# Main.net
KiCad netlist of a schematic drawn in Altium Designer
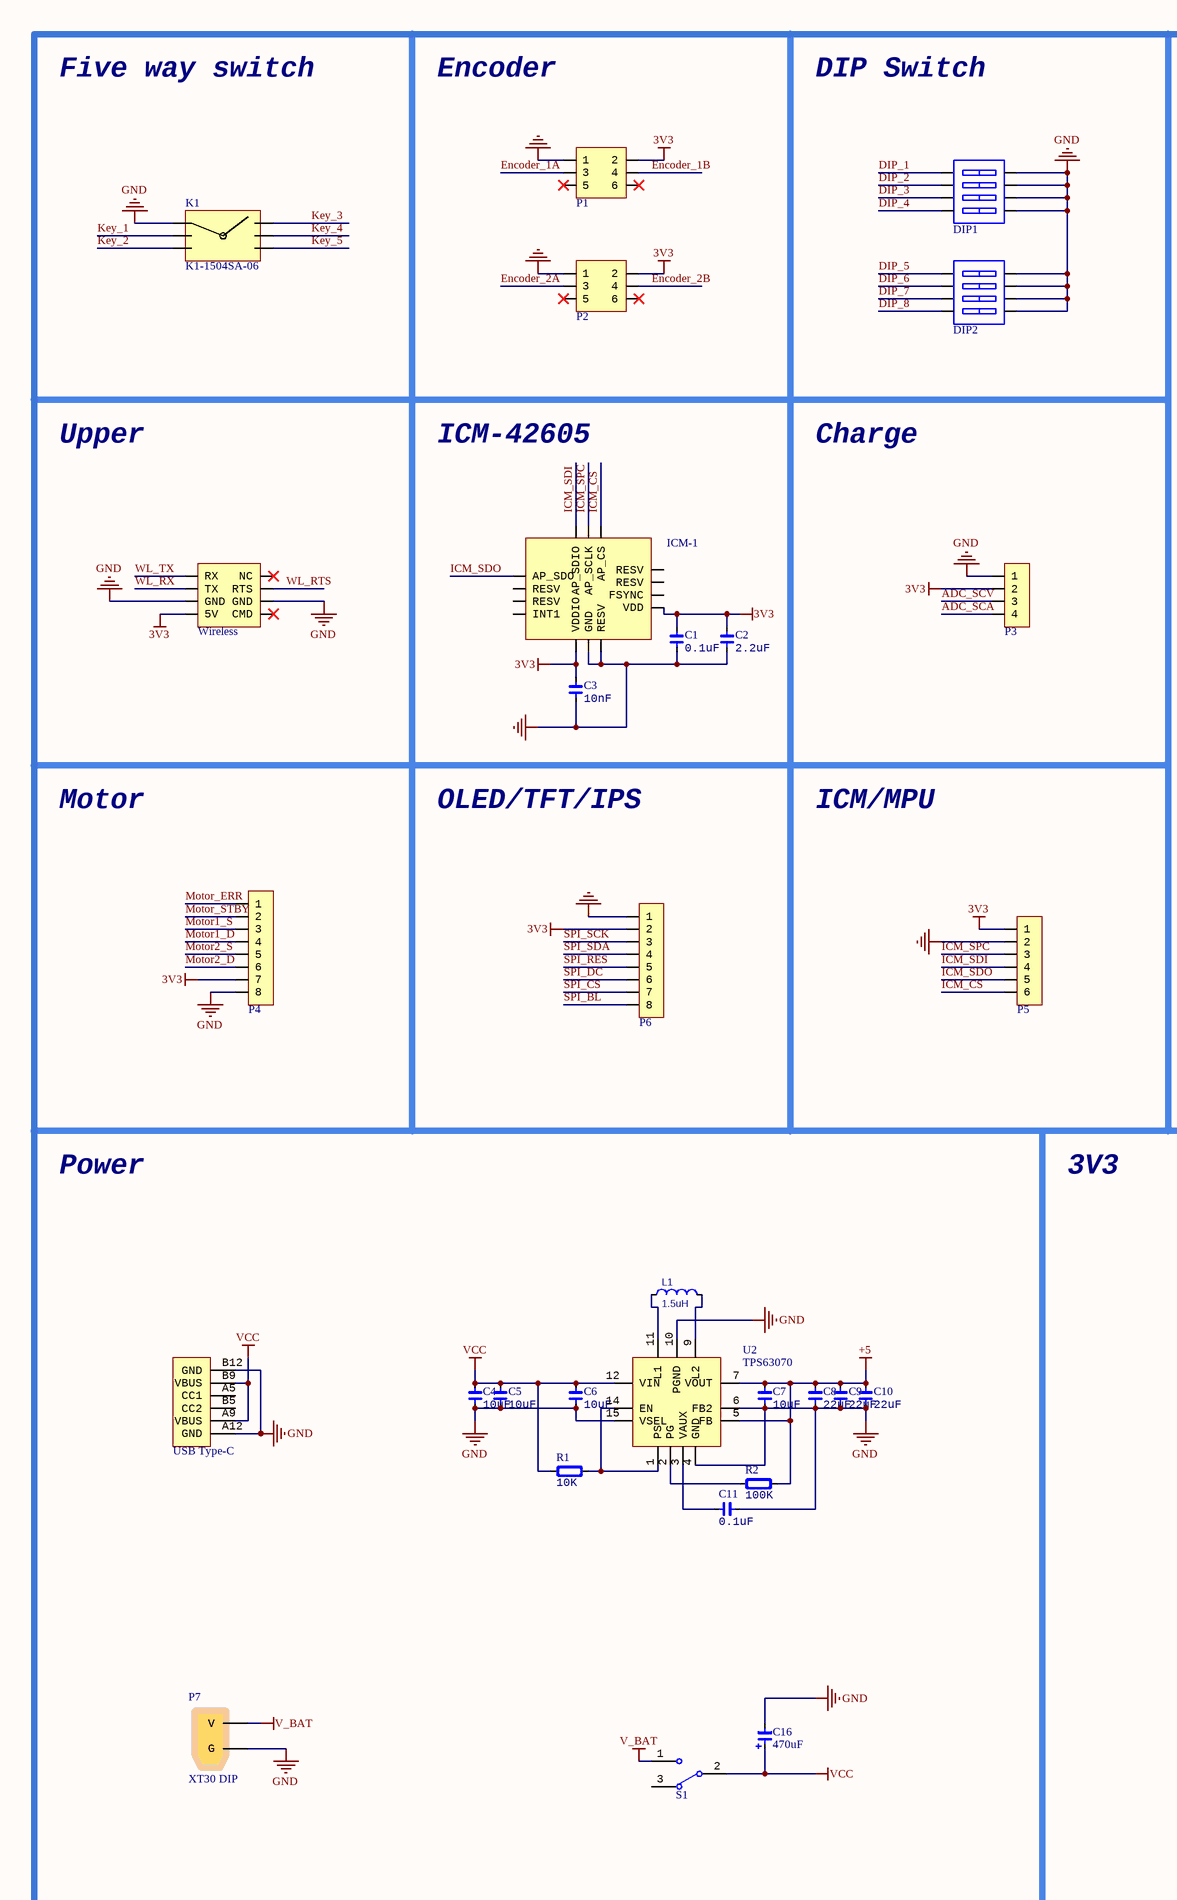
[diagram p0: Main.SchDoc, left]
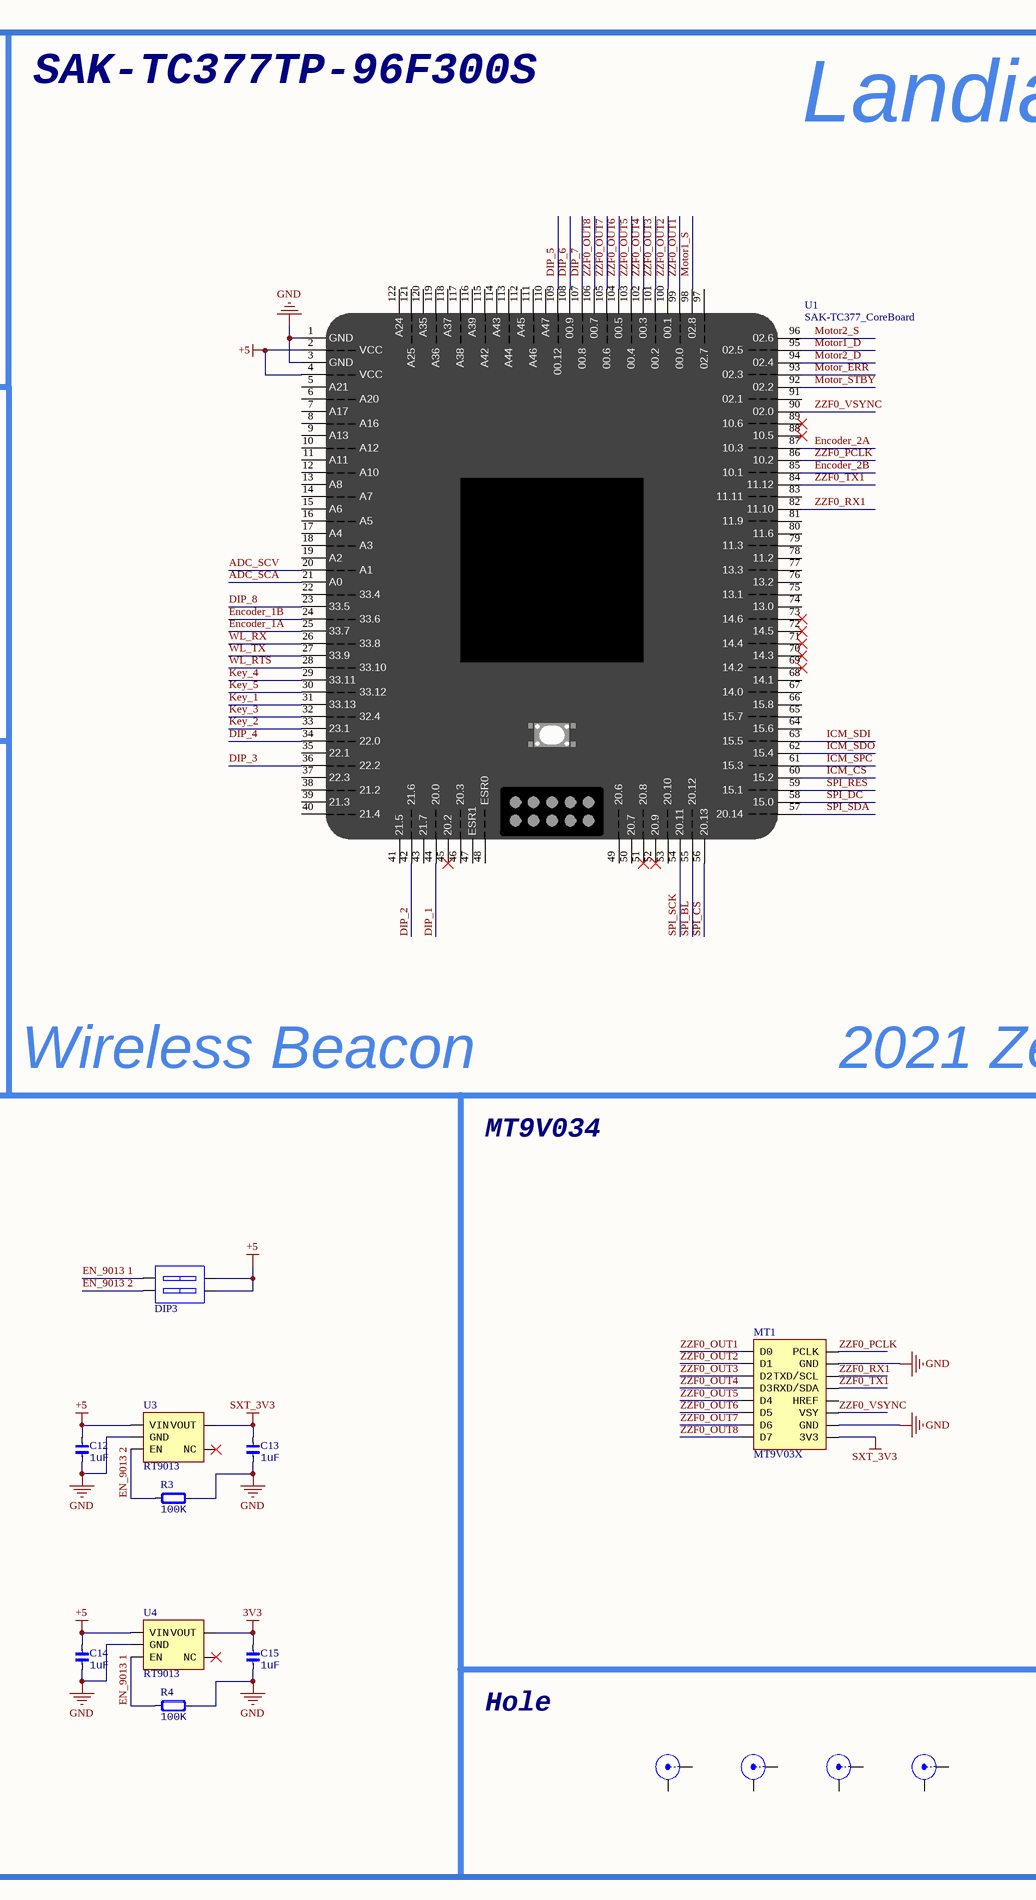
[diagram p1: Main.SchDoc, right]

(export (version "E")
  (design (tool "Eeschema 10.0.6"))
  (components
    (comp (ref "C1")
      (value "0.1uF")
      (footprint "0805_CAP")
      (description "Capacitor")
      (libsource (lib "") (part "0805_CAP_1"))
    )
    (comp (ref "C2")
      (value "2.2uF")
      (footprint "0805_CAP")
      (description "Capacitor")
      (libsource (lib "") (part "0805_CAP_1"))
    )
    (comp (ref "C3")
      (value "10nF")
      (footprint "0805_CAP")
      (description "Capacitor")
      (libsource (lib "") (part "0805_CAP_1"))
    )
    (comp (ref "C4")
      (value "10uF")
      (footprint "0805_CAP")
      (description "Capacitor")
      (libsource (lib "Beacon") (part "0805_CAP"))
    )
    (comp (ref "C5")
      (value "10uF")
      (footprint "0805_CAP")
      (description "Capacitor")
      (libsource (lib "Beacon") (part "0805_CAP"))
    )
    (comp (ref "C6")
      (value "10uF")
      (footprint "0603_CAP")
      (description "Capacitor")
      (libsource (lib "Beacon") (part "0603_CAP"))
    )
    (comp (ref "C7")
      (value "10uF")
      (footprint "0603_CAP")
      (description "Capacitor")
      (libsource (lib "Beacon") (part "0603_CAP"))
    )
    (comp (ref "C8")
      (value "22uF")
      (footprint "0805_CAP")
      (description "Capacitor")
      (libsource (lib "Beacon") (part "0805_CAP"))
    )
    (comp (ref "C9")
      (value "22uF")
      (footprint "0805_CAP")
      (description "Capacitor")
      (libsource (lib "Beacon") (part "0805_CAP"))
    )
    (comp (ref "C10")
      (value "22uF")
      (footprint "0805_CAP")
      (description "Capacitor")
      (libsource (lib "Beacon") (part "0805_CAP"))
    )
    (comp (ref "C11")
      (value "0.1uF")
      (footprint "0805_CAP")
      (description "Capacitor")
      (libsource (lib "") (part "0805_CAP_2"))
    )
    (comp (ref "C12")
      (value "1uF")
      (footprint "0805_CAP")
      (description "Capacitor")
      (libsource (lib "Beacon") (part "0805_CAP"))
    )
    (comp (ref "C13")
      (value "1uF")
      (footprint "0805_CAP")
      (description "Capacitor")
      (libsource (lib "Beacon") (part "0805_CAP"))
    )
    (comp (ref "C14")
      (value "1uF")
      (footprint "0805_CAP")
      (description "Capacitor")
      (libsource (lib "Beacon") (part "0805_CAP"))
    )
    (comp (ref "C15")
      (value "1uF")
      (footprint "0805_CAP")
      (description "Capacitor")
      (libsource (lib "Beacon") (part "0805_CAP"))
    )
    (comp (ref "C16")
      (value "470uF")
      (footprint "CAP_8X10")
      (description "Electrolytic capacitor")
      (libsource (lib "Beacon") (part "CAP_10"))
    )
    (comp (ref "DIP1")
      (value "CSW-4P_SMD")
      (footprint "DIP Switch 4P - SMD")
      (fields (field (name "版权归属") "源创客"))
      (libsource (lib "Beacon") (part "CSW-4P_SMD"))
    )
    (comp (ref "DIP2")
      (value "CSW-4P_SMD")
      (footprint "DIP Switch 4P - SMD")
      (fields (field (name "版权归属") "源创客"))
      (libsource (lib "Beacon") (part "CSW-4P_SMD"))
    )
    (comp (ref "DIP3")
      (value "CSW-2P")
      (footprint "DIP Switch 2P")
      (description "2路编码开关")
      (fields (field (name "版权归属") "源创客"))
      (libsource (lib "Beacon") (part "CSW-2P"))
    )
    (comp (ref "Hole1") (value "Hole") (footprint "Hole") (libsource (lib "Beacon") (part "Hole")))
    (comp (ref "Hole2") (value "Hole") (footprint "Hole") (libsource (lib "Beacon") (part "Hole")))
    (comp (ref "Hole3") (value "Hole") (footprint "Hole") (libsource (lib "Beacon") (part "Hole")))
    (comp (ref "Hole4") (value "Hole") (footprint "Hole") (libsource (lib "Beacon") (part "Hole")))
    (comp (ref "ICM-1")
      (value "ICM-42605")
      (footprint "LGA-14_L3.0-W2.5-P0.50-TL")
      (libsource (lib "Beacon") (part "ICM-42605"))
    )
    (comp (ref "K1")
      (value "K1-1504SA-06")
      (footprint "SW-SMD_K1-1504SA-06")
      (description "K1-1504SA-06 五向开关")
      (libsource (lib "Beacon") (part "K1-1504SA-06"))
    )
    (comp (ref "L1")
      (value "1.5uH")
      (footprint "CDRH74R")
      (description "Inductor")
      (fields
        (field (name "BOM_SUPPLIER PART") "C696490")
        (field (name "BOM_MANUFACTURER PART") "MPIT6045-330M-LF")
        (field (name "CONTRIBUTOR") "LCSC")
      )
      (libsource (lib "Beacon") (part "IND"))
    )
    (comp (ref "MT1")
      (value "MT9V03X")
      (footprint "MT9V034")
      (description "MT9V03X转接板")
      (libsource (lib "Beacon") (part "MT9V03X"))
    )
    (comp (ref "P1")
      (value "HDR2x3_2.54")
      (footprint "HDR_2X3")
      (description "Header")
      (libsource (lib "TC264DA") (part "HDR2x3_2.54"))
    )
    (comp (ref "P2")
      (value "HDR2x3_2.54")
      (footprint "HDR_2X3")
      (description "Header")
      (libsource (lib "TC264DA") (part "HDR2x3_2.54"))
    )
    (comp (ref "P3")
      (value "HDR1x4_2.54")
      (footprint "HDR_1X4")
      (description "Header")
      (libsource (lib "Beacon") (part "HDR1x4_2.54"))
    )
    (comp (ref "P4")
      (value "HDR1x8_2.54_F")
      (footprint "HDR_1X8_F")
      (description "Header")
      (libsource (lib "Beacon") (part "HDR1x8_2.54_F"))
    )
    (comp (ref "P5")
      (value "HDR1x6_2.54")
      (footprint "HDR_1X6")
      (description "Header")
      (libsource (lib "Beacon") (part "HDR1x6_2.54"))
    )
    (comp (ref "P6")
      (value "HDR1x8_2.54_F")
      (footprint "HDR_1X8_F")
      (description "Header")
      (libsource (lib "Beacon") (part "HDR1x8_2.54_F"))
    )
    (comp (ref "P7")
      (value "XT30 DIP")
      (footprint "XT30 DIP")
      (description "XT30 板载直头直插")
      (libsource (lib "Beacon") (part "XT30 DIP"))
    )
    (comp (ref "R1")
      (value "10K")
      (footprint "0805_RES")
      (description "Resistor")
      (libsource (lib "Beacon") (part "0805_RES"))
    )
    (comp (ref "R2")
      (value "100K")
      (footprint "0805_RES")
      (description "Resistor")
      (libsource (lib "Beacon") (part "0805_RES"))
    )
    (comp (ref "R3")
      (value "100K")
      (footprint "0805_RES")
      (description "Resistor")
      (libsource (lib "Beacon") (part "0805_RES"))
    )
    (comp (ref "R4")
      (value "100K")
      (footprint "0805_RES")
      (description "Resistor")
      (libsource (lib "Beacon") (part "0805_RES"))
    )
    (comp (ref "S1") (value "SMTS-102") (footprint "SMTS-102") (libsource (lib "Beacon") (part "SMTS-102")))
    (comp (ref "Type-C1")
      (value "USB Type-C")
      (footprint "Type-C 6P")
      (description "Type-C 6P")
      (libsource (lib "Beacon") (part "USB_Type-C_6P"))
    )
    (comp (ref "U1")
      (value "SAK-TC377_CoreBoard")
      (footprint "TC377_CoreBoard")
      (description "逐飞科技TC377核心板")
      (libsource (lib "Beacon") (part "SAK-TC377_CoreBoard"))
    )
    (comp (ref "U2")
      (value "TPS63070")
      (footprint "VQFN-15_L3.0-W2.5-P0.50-BL")
      (libsource (lib "Beacon") (part "TPS63070"))
    )
    (comp (ref "U3")
      (value "RT9013")
      (footprint "SOT-23-5_L3.0-W1.7-P0.95-LS2.8-BR")
      (libsource (lib "Beacon") (part "RT9013"))
    )
    (comp (ref "U4")
      (value "RT9013")
      (footprint "SOT-23-5_L3.0-W1.7-P0.95-LS2.8-BR")
      (libsource (lib "Beacon") (part "RT9013"))
    )
    (comp (ref "Wireless1")
      (value "Wireless")
      (footprint "HDR_2X4_F")
      (libsource (lib "Beacon") (part "Wireless"))
    )
  )
  (nets
    (net (code "1") (name "+5") (class "Default")
      (node (ref "C10") (pin "2") (pinfunction "2_2") (pintype "passive"))
      (node (ref "C12") (pin "2") (pinfunction "2_2") (pintype "passive"))
      (node (ref "C14") (pin "2") (pinfunction "2_2") (pintype "passive"))
      (node (ref "C7") (pin "2") (pinfunction "2_2") (pintype "passive"))
      (node (ref "C8") (pin "2") (pinfunction "2_2") (pintype "passive"))
      (node (ref "C9") (pin "2") (pinfunction "2_2") (pintype "passive"))
      (node (ref "DIP3") (pin "4") (pinfunction "4_4") (pintype "passive"))
      (node (ref "DIP3") (pin "5") (pinfunction "5_5") (pintype "passive"))
      (node (ref "R2") (pin "2") (pinfunction "2_2") (pintype "passive"))
      (node (ref "U1") (pin "2") (pinfunction "VCC_2") (pintype "passive"))
      (node (ref "U1") (pin "4") (pinfunction "VCC_4") (pintype "passive"))
      (node (ref "U2") (pin "5") (pinfunction "FB_5") (pintype "passive"))
      (node (ref "U2") (pin "7") (pinfunction "VOUT_7") (pintype "passive"))
      (node (ref "U3") (pin "1") (pinfunction "VIN_1") (pintype "passive"))
      (node (ref "U4") (pin "1") (pinfunction "VIN_1") (pintype "passive"))
    )
    (net (code "2") (name "/ADC_SCA") (class "Default")
      (node (ref "P3") (pin "4") (pinfunction "4_4") (pintype "passive"))
      (node (ref "U1") (pin "21") (pinfunction "A0_21") (pintype "passive"))
    )
    (net (code "3") (name "/ADC_SCV") (class "Default")
      (node (ref "P3") (pin "3") (pinfunction "3_3") (pintype "passive"))
      (node (ref "U1") (pin "20") (pinfunction "A1_20") (pintype "passive"))
    )
    (net (code "4") (name "/DIP_1") (class "Default")
      (node (ref "DIP1") (pin "1") (pinfunction "1_1") (pintype "passive"))
      (node (ref "U1") (pin "44") (pinfunction "20.0_44") (pintype "passive"))
    )
    (net (code "5") (name "/DIP_2") (class "Default")
      (node (ref "DIP1") (pin "2") (pinfunction "2_2") (pintype "passive"))
      (node (ref "U1") (pin "42") (pinfunction "21.6_42") (pintype "passive"))
    )
    (net (code "6") (name "/DIP_3") (class "Default")
      (node (ref "DIP1") (pin "3") (pinfunction "3_3") (pintype "passive"))
      (node (ref "U1") (pin "36") (pinfunction "22.2_36") (pintype "passive"))
    )
    (net (code "7") (name "/DIP_4") (class "Default")
      (node (ref "DIP1") (pin "4") (pinfunction "4_4") (pintype "passive"))
      (node (ref "U1") (pin "34") (pinfunction "22.0_34") (pintype "passive"))
    )
    (net (code "8") (name "/DIP_5") (class "Default")
      (node (ref "DIP2") (pin "1") (pinfunction "1_1") (pintype "passive"))
      (node (ref "U1") (pin "109") (pinfunction "00.12_109") (pintype "passive"))
    )
    (net (code "9") (name "/DIP_6") (class "Default")
      (node (ref "DIP2") (pin "2") (pinfunction "2_2") (pintype "passive"))
      (node (ref "U1") (pin "108") (pinfunction "00.9_108") (pintype "passive"))
    )
    (net (code "10") (name "/DIP_7") (class "Default")
      (node (ref "DIP2") (pin "3") (pinfunction "3_3") (pintype "passive"))
      (node (ref "U1") (pin "107") (pinfunction "00.8_107") (pintype "passive"))
    )
    (net (code "11") (name "/DIP_8") (class "Default")
      (node (ref "DIP2") (pin "4") (pinfunction "4_4") (pintype "passive"))
      (node (ref "U1") (pin "23") (pinfunction "33.5_23") (pintype "passive"))
    )
    (net (code "12") (name "/EN_9013 1") (class "Default")
      (node (ref "DIP3") (pin "1") (pinfunction "1_1") (pintype "passive"))
      (node (ref "R4") (pin "1") (pinfunction "1_1") (pintype "passive"))
      (node (ref "U4") (pin "3") (pinfunction "EN_3") (pintype "passive"))
    )
    (net (code "13") (name "/EN_9013 2") (class "Default")
      (node (ref "DIP3") (pin "2") (pinfunction "2_2") (pintype "passive"))
      (node (ref "R3") (pin "1") (pinfunction "1_1") (pintype "passive"))
      (node (ref "U3") (pin "3") (pinfunction "EN_3") (pintype "passive"))
    )
    (net (code "14") (name "/Encoder_1A") (class "Default")
      (node (ref "P1") (pin "3") (pinfunction "3_3") (pintype "passive"))
      (node (ref "U1") (pin "25") (pinfunction "33.7_25") (pintype "passive"))
    )
    (net (code "15") (name "/Encoder_1B") (class "Default")
      (node (ref "P1") (pin "4") (pinfunction "4_4") (pintype "passive"))
      (node (ref "U1") (pin "24") (pinfunction "33.6_24") (pintype "passive"))
    )
    (net (code "16") (name "/Encoder_2A") (class "Default")
      (node (ref "P2") (pin "3") (pinfunction "3_3") (pintype "passive"))
      (node (ref "U1") (pin "87") (pinfunction "10.3_87") (pintype "passive"))
    )
    (net (code "17") (name "/Encoder_2B") (class "Default")
      (node (ref "P2") (pin "4") (pinfunction "4_4") (pintype "passive"))
      (node (ref "U1") (pin "85") (pinfunction "10.1_85") (pintype "passive"))
    )
    (net (code "18") (name "/ICM_CS") (class "Default")
      (node (ref "ICM-1") (pin "12") (pinfunction "AP_CS_12") (pintype "passive"))
      (node (ref "P5") (pin "6") (pinfunction "6_6") (pintype "passive"))
      (node (ref "U1") (pin "60") (pinfunction "15.2_60") (pintype "passive"))
    )
    (net (code "19") (name "/ICM_SDI") (class "Default")
      (node (ref "ICM-1") (pin "14") (pinfunction "AP_SDIO_14") (pintype "passive"))
      (node (ref "P5") (pin "4") (pinfunction "4_4") (pintype "passive"))
      (node (ref "U1") (pin "63") (pinfunction "15.5_63") (pintype "passive"))
    )
    (net (code "20") (name "/ICM_SDO") (class "Default")
      (node (ref "ICM-1") (pin "1") (pinfunction "AP_SDO_1") (pintype "passive"))
      (node (ref "P5") (pin "5") (pinfunction "5_5") (pintype "passive"))
      (node (ref "U1") (pin "62") (pinfunction "15.4_62") (pintype "passive"))
    )
    (net (code "21") (name "/ICM_SPC") (class "Default")
      (node (ref "ICM-1") (pin "13") (pinfunction "AP_SCLK_13") (pintype "passive"))
      (node (ref "P5") (pin "3") (pinfunction "3_3") (pintype "passive"))
      (node (ref "U1") (pin "61") (pinfunction "15.3_61") (pintype "passive"))
    )
    (net (code "22") (name "/Key_1") (class "Default")
      (node (ref "K1") (pin "2") (pinfunction "2_2") (pintype "passive"))
      (node (ref "U1") (pin "31") (pinfunction "33.13_31") (pintype "passive"))
    )
    (net (code "23") (name "/Key_2") (class "Default")
      (node (ref "K1") (pin "3") (pinfunction "3_3") (pintype "passive"))
      (node (ref "U1") (pin "33") (pinfunction "23.1_33") (pintype "passive"))
    )
    (net (code "24") (name "/Key_3") (class "Default")
      (node (ref "K1") (pin "4") (pinfunction "4_4") (pintype "passive"))
      (node (ref "U1") (pin "32") (pinfunction "32.4_32") (pintype "passive"))
    )
    (net (code "25") (name "/Key_4") (class "Default")
      (node (ref "K1") (pin "5") (pinfunction "5_5") (pintype "passive"))
      (node (ref "U1") (pin "29") (pinfunction "33.11_29") (pintype "passive"))
    )
    (net (code "26") (name "/Key_5") (class "Default")
      (node (ref "K1") (pin "6") (pinfunction "6_6") (pintype "passive"))
      (node (ref "U1") (pin "30") (pinfunction "33.12_30") (pintype "passive"))
    )
    (net (code "27") (name "/Motor1_D") (class "Default")
      (node (ref "P4") (pin "4") (pinfunction "4_4") (pintype "passive"))
      (node (ref "U1") (pin "95") (pinfunction "02.5_95") (pintype "passive"))
    )
    (net (code "28") (name "/Motor1_S") (class "Default")
      (node (ref "P4") (pin "3") (pinfunction "3_3") (pintype "passive"))
      (node (ref "U1") (pin "98") (pinfunction "02.8_98") (pintype "passive"))
    )
    (net (code "29") (name "/Motor2_D") (class "Default")
      (node (ref "P4") (pin "6") (pinfunction "6_6") (pintype "passive"))
      (node (ref "U1") (pin "94") (pinfunction "02.4_94") (pintype "passive"))
    )
    (net (code "30") (name "/Motor2_S") (class "Default")
      (node (ref "P4") (pin "5") (pinfunction "5_5") (pintype "passive"))
      (node (ref "U1") (pin "96") (pinfunction "02.6_96") (pintype "passive"))
    )
    (net (code "31") (name "/Motor_ERR") (class "Default")
      (node (ref "P4") (pin "1") (pinfunction "1_1") (pintype "passive"))
      (node (ref "U1") (pin "93") (pinfunction "02.3_93") (pintype "passive"))
    )
    (net (code "32") (name "/Motor_STBY") (class "Default")
      (node (ref "P4") (pin "2") (pinfunction "2_2") (pintype "passive"))
      (node (ref "U1") (pin "92") (pinfunction "02.2_92") (pintype "passive"))
    )
    (net (code "33") (name "/SPI_BL") (class "Default")
      (node (ref "P6") (pin "8") (pinfunction "8_8") (pintype "passive"))
      (node (ref "U1") (pin "55") (pinfunction "20.12_55") (pintype "passive"))
    )
    (net (code "34") (name "/SPI_CS") (class "Default")
      (node (ref "P6") (pin "7") (pinfunction "7_7") (pintype "passive"))
      (node (ref "U1") (pin "56") (pinfunction "20.13_56") (pintype "passive"))
    )
    (net (code "35") (name "/SPI_DC") (class "Default")
      (node (ref "P6") (pin "6") (pinfunction "6_6") (pintype "passive"))
      (node (ref "U1") (pin "58") (pinfunction "15.0_58") (pintype "passive"))
    )
    (net (code "36") (name "/SPI_RES") (class "Default")
      (node (ref "P6") (pin "5") (pinfunction "5_5") (pintype "passive"))
      (node (ref "U1") (pin "59") (pinfunction "15.1_59") (pintype "passive"))
    )
    (net (code "37") (name "/SPI_SCK") (class "Default")
      (node (ref "P6") (pin "3") (pinfunction "3_3") (pintype "passive"))
      (node (ref "U1") (pin "54") (pinfunction "20.11_54") (pintype "passive"))
    )
    (net (code "38") (name "/SPI_SDA") (class "Default")
      (node (ref "P6") (pin "4") (pinfunction "4_4") (pintype "passive"))
      (node (ref "U1") (pin "57") (pinfunction "20.14_57") (pintype "passive"))
    )
    (net (code "39") (name "/WL_RTS") (class "Default")
      (node (ref "U1") (pin "28") (pinfunction "33.10_28") (pintype "passive"))
      (node (ref "Wireless1") (pin "4") (pinfunction "RTS_4") (pintype "passive"))
    )
    (net (code "40") (name "/WL_RX") (class "Default")
      (node (ref "U1") (pin "26") (pinfunction "33.8_26") (pintype "passive"))
      (node (ref "Wireless1") (pin "3") (pinfunction "TX_3") (pintype "passive"))
    )
    (net (code "41") (name "/WL_TX") (class "Default")
      (node (ref "U1") (pin "27") (pinfunction "33.9_27") (pintype "passive"))
      (node (ref "Wireless1") (pin "1") (pinfunction "RX_1") (pintype "passive"))
    )
    (net (code "42") (name "/ZZF0_OUT1") (class "Default")
      (node (ref "MT1") (pin "1") (pinfunction "D0_1") (pintype "passive"))
      (node (ref "U1") (pin "99") (pinfunction "00.0_99") (pintype "passive"))
    )
    (net (code "43") (name "/ZZF0_OUT2") (class "Default")
      (node (ref "MT1") (pin "3") (pinfunction "D1_3") (pintype "passive"))
      (node (ref "U1") (pin "100") (pinfunction "00.1_100") (pintype "passive"))
    )
    (net (code "44") (name "/ZZF0_OUT3") (class "Default")
      (node (ref "MT1") (pin "5") (pinfunction "D2_5") (pintype "passive"))
      (node (ref "U1") (pin "101") (pinfunction "00.2_101") (pintype "passive"))
    )
    (net (code "45") (name "/ZZF0_OUT4") (class "Default")
      (node (ref "MT1") (pin "7") (pinfunction "D3_7") (pintype "passive"))
      (node (ref "U1") (pin "102") (pinfunction "00.3_102") (pintype "passive"))
    )
    (net (code "46") (name "/ZZF0_OUT5") (class "Default")
      (node (ref "MT1") (pin "9") (pinfunction "D4_9") (pintype "passive"))
      (node (ref "U1") (pin "103") (pinfunction "00.4_103") (pintype "passive"))
    )
    (net (code "47") (name "/ZZF0_OUT6") (class "Default")
      (node (ref "MT1") (pin "11") (pinfunction "D5_11") (pintype "passive"))
      (node (ref "U1") (pin "104") (pinfunction "00.5_104") (pintype "passive"))
    )
    (net (code "48") (name "/ZZF0_OUT7") (class "Default")
      (node (ref "MT1") (pin "13") (pinfunction "D6_13") (pintype "passive"))
      (node (ref "U1") (pin "105") (pinfunction "00.6_105") (pintype "passive"))
    )
    (net (code "49") (name "/ZZF0_OUT8") (class "Default")
      (node (ref "MT1") (pin "15") (pinfunction "D7_15") (pintype "passive"))
      (node (ref "U1") (pin "106") (pinfunction "00.7_106") (pintype "passive"))
    )
    (net (code "50") (name "/ZZF0_PCLK") (class "Default")
      (node (ref "MT1") (pin "2") (pinfunction "PCLK_2") (pintype "passive"))
      (node (ref "U1") (pin "86") (pinfunction "10.2_86") (pintype "passive"))
    )
    (net (code "51") (name "/ZZF0_RX1") (class "Default")
      (node (ref "MT1") (pin "6") (pinfunction "TXD/SCL_6") (pintype "passive"))
      (node (ref "U1") (pin "82") (pinfunction "11.10_82") (pintype "passive"))
    )
    (net (code "52") (name "/ZZF0_TX1") (class "Default")
      (node (ref "MT1") (pin "8") (pinfunction "RXD/SDA_8") (pintype "passive"))
      (node (ref "U1") (pin "84") (pinfunction "11.12_84") (pintype "passive"))
    )
    (net (code "53") (name "/ZZF0_VSYNC") (class "Default")
      (node (ref "MT1") (pin "12") (pinfunction "VSY_12") (pintype "passive"))
      (node (ref "U1") (pin "90") (pinfunction "02.0_90") (pintype "passive"))
    )
    (net (code "54") (name "3V3") (class "Default")
      (node (ref "C1") (pin "1") (pinfunction "1_1") (pintype "passive"))
      (node (ref "C15") (pin "2") (pinfunction "2_2") (pintype "passive"))
      (node (ref "C2") (pin "1") (pinfunction "1_1") (pintype "passive"))
      (node (ref "C3") (pin "1") (pinfunction "1_1") (pintype "passive"))
      (node (ref "ICM-1") (pin "5") (pinfunction "VDDIO_5") (pintype "passive"))
      (node (ref "ICM-1") (pin "8") (pinfunction "VDD_8") (pintype "passive"))
      (node (ref "P1") (pin "2") (pinfunction "2_2") (pintype "passive"))
      (node (ref "P2") (pin "2") (pinfunction "2_2") (pintype "passive"))
      (node (ref "P3") (pin "2") (pinfunction "2_2") (pintype "passive"))
      (node (ref "P4") (pin "7") (pinfunction "7_7") (pintype "passive"))
      (node (ref "P5") (pin "1") (pinfunction "1_1") (pintype "passive"))
      (node (ref "P6") (pin "2") (pinfunction "2_2") (pintype "passive"))
      (node (ref "U4") (pin "5") (pinfunction "VOUT_5") (pintype "passive"))
      (node (ref "Wireless1") (pin "7") (pinfunction "5V_7") (pintype "passive"))
    )
    (net (code "55") (name "GND") (class "Default")
      (node (ref "C1") (pin "2") (pinfunction "2_2") (pintype "passive"))
      (node (ref "C10") (pin "1") (pinfunction "1_1") (pintype "passive"))
      (node (ref "C11") (pin "1") (pinfunction "1_1") (pintype "passive"))
      (node (ref "C12") (pin "1") (pinfunction "1_1") (pintype "passive"))
      (node (ref "C13") (pin "1") (pinfunction "1_1") (pintype "passive"))
      (node (ref "C14") (pin "1") (pinfunction "1_1") (pintype "passive"))
      (node (ref "C15") (pin "1") (pinfunction "1_1") (pintype "passive"))
      (node (ref "C16") (pin "2") (pinfunction "2_2") (pintype "passive"))
      (node (ref "C2") (pin "2") (pinfunction "2_2") (pintype "passive"))
      (node (ref "C3") (pin "2") (pinfunction "2_2") (pintype "passive"))
      (node (ref "C4") (pin "1") (pinfunction "1_1") (pintype "passive"))
      (node (ref "C5") (pin "1") (pinfunction "1_1") (pintype "passive"))
      (node (ref "C6") (pin "1") (pinfunction "1_1") (pintype "passive"))
      (node (ref "C7") (pin "1") (pinfunction "1_1") (pintype "passive"))
      (node (ref "C8") (pin "1") (pinfunction "1_1") (pintype "passive"))
      (node (ref "C9") (pin "1") (pinfunction "1_1") (pintype "passive"))
      (node (ref "DIP1") (pin "5") (pinfunction "5_5") (pintype "passive"))
      (node (ref "DIP1") (pin "6") (pinfunction "6_6") (pintype "passive"))
      (node (ref "DIP1") (pin "7") (pinfunction "7_7") (pintype "passive"))
      (node (ref "DIP1") (pin "8") (pinfunction "8_8") (pintype "passive"))
      (node (ref "DIP2") (pin "5") (pinfunction "5_5") (pintype "passive"))
      (node (ref "DIP2") (pin "6") (pinfunction "6_6") (pintype "passive"))
      (node (ref "DIP2") (pin "7") (pinfunction "7_7") (pintype "passive"))
      (node (ref "DIP2") (pin "8") (pinfunction "8_8") (pintype "passive"))
      (node (ref "ICM-1") (pin "6") (pinfunction "GND_6") (pintype "passive"))
      (node (ref "ICM-1") (pin "7") (pinfunction "RESV_7") (pintype "passive"))
      (node (ref "K1") (pin "1") (pinfunction "1_1") (pintype "passive"))
      (node (ref "MT1") (pin "14") (pinfunction "GND_14") (pintype "passive"))
      (node (ref "MT1") (pin "4") (pinfunction "GND_4") (pintype "passive"))
      (node (ref "P1") (pin "1") (pinfunction "1_1") (pintype "passive"))
      (node (ref "P2") (pin "1") (pinfunction "1_1") (pintype "passive"))
      (node (ref "P3") (pin "1") (pinfunction "1_1") (pintype "passive"))
      (node (ref "P4") (pin "8") (pinfunction "8_8") (pintype "passive"))
      (node (ref "P5") (pin "2") (pinfunction "2_2") (pintype "passive"))
      (node (ref "P6") (pin "1") (pinfunction "1_1") (pintype "passive"))
      (node (ref "P7") (pin "2") (pinfunction "G_2") (pintype "passive"))
      (node (ref "R3") (pin "2") (pinfunction "2_2") (pintype "passive"))
      (node (ref "R4") (pin "2") (pinfunction "2_2") (pintype "passive"))
      (node (ref "Type-C1") (pin "A12") (pinfunction "GND_A12") (pintype "passive"))
      (node (ref "Type-C1") (pin "B12") (pinfunction "GND_B12") (pintype "passive"))
      (node (ref "U1") (pin "1") (pinfunction "GND_1") (pintype "passive"))
      (node (ref "U1") (pin "3") (pinfunction "GND_3") (pintype "passive"))
      (node (ref "U2") (pin "10") (pinfunction "PGND_10") (pintype "passive"))
      (node (ref "U2") (pin "15") (pinfunction "VSEL_15") (pintype "passive"))
      (node (ref "U2") (pin "4") (pinfunction "GND_4") (pintype "passive"))
      (node (ref "U2") (pin "6") (pinfunction "FB2_6") (pintype "passive"))
      (node (ref "U3") (pin "2") (pinfunction "GND_2") (pintype "passive"))
      (node (ref "U4") (pin "2") (pinfunction "GND_2") (pintype "passive"))
      (node (ref "Wireless1") (pin "5") (pinfunction "GND_5") (pintype "passive"))
      (node (ref "Wireless1") (pin "6") (pinfunction "GND_6") (pintype "passive"))
    )
    (net (code "56") (name "Net-(U2-EN)") (class "Default")
      (node (ref "R1") (pin "2") (pinfunction "2_2") (pintype "passive"))
      (node (ref "U2") (pin "1") (pinfunction "PS_1") (pintype "passive"))
      (node (ref "U2") (pin "14") (pinfunction "EN_14") (pintype "passive"))
    )
    (net (code "57") (name "Net-(U2-L1)") (class "Default")
      (node (ref "L1") (pin "1") (pinfunction "1_1") (pintype "passive"))
      (node (ref "U2") (pin "11") (pinfunction "L1_11") (pintype "passive"))
    )
    (net (code "58") (name "Net-(U2-L2)") (class "Default")
      (node (ref "L1") (pin "2") (pinfunction "2_2") (pintype "passive"))
      (node (ref "U2") (pin "9") (pinfunction "L2_9") (pintype "passive"))
    )
    (net (code "59") (name "Net-(U2-PG)") (class "Default")
      (node (ref "R2") (pin "1") (pinfunction "1_1") (pintype "passive"))
      (node (ref "U2") (pin "2") (pinfunction "PG_2") (pintype "passive"))
    )
    (net (code "60") (name "Net-(U2-VAUX)") (class "Default")
      (node (ref "C11") (pin "2") (pinfunction "2_2") (pintype "passive"))
      (node (ref "U2") (pin "3") (pinfunction "VAUX_3") (pintype "passive"))
    )
    (net (code "61") (name "SXT_3V3") (class "Default")
      (node (ref "C13") (pin "2") (pinfunction "2_2") (pintype "passive"))
      (node (ref "MT1") (pin "16") (pinfunction "3V3_16") (pintype "passive"))
      (node (ref "U3") (pin "5") (pinfunction "VOUT_5") (pintype "passive"))
    )
    (net (code "62") (name "VCC") (class "Default")
      (node (ref "C16") (pin "1") (pinfunction "1_1") (pintype "passive"))
      (node (ref "C4") (pin "2") (pinfunction "2_2") (pintype "passive"))
      (node (ref "C5") (pin "2") (pinfunction "2_2") (pintype "passive"))
      (node (ref "C6") (pin "2") (pinfunction "2_2") (pintype "passive"))
      (node (ref "R1") (pin "1") (pinfunction "1_1") (pintype "passive"))
      (node (ref "S1") (pin "2") (pinfunction "2_2") (pintype "passive"))
      (node (ref "Type-C1") (pin "A9") (pinfunction "VBUS_A9") (pintype "passive"))
      (node (ref "Type-C1") (pin "B9") (pinfunction "VBUS_B9") (pintype "passive"))
      (node (ref "U2") (pin "12") (pinfunction "VIN_12") (pintype "passive"))
    )
    (net (code "63") (name "V_BAT") (class "Default")
      (node (ref "P7") (pin "1") (pinfunction "V_1") (pintype "passive"))
      (node (ref "S1") (pin "1") (pinfunction "1_1") (pintype "passive"))
    )
    (net (code "64") (name "unconnected-(Hole1-X-Pad1)") (class "Default")
      (node (ref "Hole1") (pin "1") (pinfunction "X_1") (pintype "passive"))
    )
    (net (code "65") (name "unconnected-(Hole1-Y-Pad2)") (class "Default")
      (node (ref "Hole1") (pin "2") (pinfunction "Y_2") (pintype "passive"))
    )
    (net (code "66") (name "unconnected-(Hole2-X-Pad1)") (class "Default")
      (node (ref "Hole2") (pin "1") (pinfunction "X_1") (pintype "passive"))
    )
    (net (code "67") (name "unconnected-(Hole2-Y-Pad2)") (class "Default")
      (node (ref "Hole2") (pin "2") (pinfunction "Y_2") (pintype "passive"))
    )
    (net (code "68") (name "unconnected-(Hole3-X-Pad1)") (class "Default")
      (node (ref "Hole3") (pin "1") (pinfunction "X_1") (pintype "passive"))
    )
    (net (code "69") (name "unconnected-(Hole3-Y-Pad2)") (class "Default")
      (node (ref "Hole3") (pin "2") (pinfunction "Y_2") (pintype "passive"))
    )
    (net (code "70") (name "unconnected-(Hole4-X-Pad1)") (class "Default")
      (node (ref "Hole4") (pin "1") (pinfunction "X_1") (pintype "passive"))
    )
    (net (code "71") (name "unconnected-(Hole4-Y-Pad2)") (class "Default")
      (node (ref "Hole4") (pin "2") (pinfunction "Y_2") (pintype "passive"))
    )
    (net (code "72") (name "unconnected-(ICM-1-FSYNC-Pad9)") (class "Default")
      (node (ref "ICM-1") (pin "9") (pinfunction "FSYNC_9") (pintype "passive"))
    )
    (net (code "73") (name "unconnected-(ICM-1-INT1-Pad4)") (class "Default")
      (node (ref "ICM-1") (pin "4") (pinfunction "INT1_4") (pintype "passive"))
    )
    (net (code "74") (name "unconnected-(ICM-1-RESV-Pad2)") (class "Default")
      (node (ref "ICM-1") (pin "2") (pinfunction "RESV_2") (pintype "passive"))
    )
    (net (code "75") (name "unconnected-(ICM-1-RESV-Pad3)") (class "Default")
      (node (ref "ICM-1") (pin "3") (pinfunction "RESV_3") (pintype "passive"))
    )
    (net (code "76") (name "unconnected-(ICM-1-RESV-Pad10)") (class "Default")
      (node (ref "ICM-1") (pin "10") (pinfunction "RESV_10") (pintype "passive"))
    )
    (net (code "77") (name "unconnected-(ICM-1-RESV-Pad11)") (class "Default")
      (node (ref "ICM-1") (pin "11") (pinfunction "RESV_11") (pintype "passive"))
    )
    (net (code "78") (name "unconnected-(MT1-HREF-Pad10)") (class "Default")
      (node (ref "MT1") (pin "10") (pinfunction "HREF_10") (pintype "passive"))
    )
    (net (code "79") (name "unconnected-(P1-Pad5)") (class "Default")
      (node (ref "P1") (pin "5") (pinfunction "5_5") (pintype "passive+no_connect"))
    )
    (net (code "80") (name "unconnected-(P1-Pad6)") (class "Default")
      (node (ref "P1") (pin "6") (pinfunction "6_6") (pintype "passive+no_connect"))
    )
    (net (code "81") (name "unconnected-(P2-Pad5)") (class "Default")
      (node (ref "P2") (pin "5") (pinfunction "5_5") (pintype "passive+no_connect"))
    )
    (net (code "82") (name "unconnected-(P2-Pad6)") (class "Default")
      (node (ref "P2") (pin "6") (pinfunction "6_6") (pintype "passive+no_connect"))
    )
    (net (code "83") (name "unconnected-(S1-Pad3)") (class "Default")
      (node (ref "S1") (pin "3") (pinfunction "3_3") (pintype "passive"))
    )
    (net (code "84") (name "unconnected-(Type-C1-CC1-PadA5)") (class "Default")
      (node (ref "Type-C1") (pin "A5") (pinfunction "CC1_A5") (pintype "passive"))
    )
    (net (code "85") (name "unconnected-(Type-C1-CC2-PadB5)") (class "Default")
      (node (ref "Type-C1") (pin "B5") (pinfunction "CC2_B5") (pintype "passive"))
    )
    (net (code "86") (name "unconnected-(U1-02.1-Pad91)") (class "Default")
      (node (ref "U1") (pin "91") (pinfunction "02.1_91") (pintype "passive"))
    )
    (net (code "87") (name "unconnected-(U1-02.7-Pad97)") (class "Default")
      (node (ref "U1") (pin "97") (pinfunction "02.7_97") (pintype "passive"))
    )
    (net (code "88") (name "unconnected-(U1-10.5-Pad88)") (class "Default")
      (node (ref "U1") (pin "88") (pinfunction "10.5_88") (pintype "passive+no_connect"))
    )
    (net (code "89") (name "unconnected-(U1-10.6-Pad89)") (class "Default")
      (node (ref "U1") (pin "89") (pinfunction "10.6_89") (pintype "passive+no_connect"))
    )
    (net (code "90") (name "unconnected-(U1-11.2-Pad78)") (class "Default")
      (node (ref "U1") (pin "78") (pinfunction "11.2_78") (pintype "passive"))
    )
    (net (code "91") (name "unconnected-(U1-11.3-Pad79)") (class "Default")
      (node (ref "U1") (pin "79") (pinfunction "11.3_79") (pintype "passive"))
    )
    (net (code "92") (name "unconnected-(U1-11.6-Pad80)") (class "Default")
      (node (ref "U1") (pin "80") (pinfunction "11.6_80") (pintype "passive"))
    )
    (net (code "93") (name "unconnected-(U1-11.9-Pad81)") (class "Default")
      (node (ref "U1") (pin "81") (pinfunction "11.9_81") (pintype "passive"))
    )
    (net (code "94") (name "unconnected-(U1-11.11-Pad83)") (class "Default")
      (node (ref "U1") (pin "83") (pinfunction "11.11_83") (pintype "passive"))
    )
    (net (code "95") (name "unconnected-(U1-13.0-Pad74)") (class "Default")
      (node (ref "U1") (pin "74") (pinfunction "13.0_74") (pintype "passive"))
    )
    (net (code "96") (name "unconnected-(U1-13.1-Pad75)") (class "Default")
      (node (ref "U1") (pin "75") (pinfunction "13.1_75") (pintype "passive"))
    )
    (net (code "97") (name "unconnected-(U1-13.2-Pad76)") (class "Default")
      (node (ref "U1") (pin "76") (pinfunction "13.2_76") (pintype "passive"))
    )
    (net (code "98") (name "unconnected-(U1-13.3-Pad77)") (class "Default")
      (node (ref "U1") (pin "77") (pinfunction "13.3_77") (pintype "passive"))
    )
    (net (code "99") (name "unconnected-(U1-14.0-Pad67)") (class "Default")
      (node (ref "U1") (pin "67") (pinfunction "14.0_67") (pintype "passive"))
    )
    (net (code "100") (name "unconnected-(U1-14.1-Pad68)") (class "Default")
      (node (ref "U1") (pin "68") (pinfunction "14.1_68") (pintype "passive"))
    )
    (net (code "101") (name "unconnected-(U1-14.2-Pad69)") (class "Default")
      (node (ref "U1") (pin "69") (pinfunction "14.2_69") (pintype "passive+no_connect"))
    )
    (net (code "102") (name "unconnected-(U1-14.3-Pad70)") (class "Default")
      (node (ref "U1") (pin "70") (pinfunction "14.3_70") (pintype "passive+no_connect"))
    )
    (net (code "103") (name "unconnected-(U1-14.4-Pad71)") (class "Default")
      (node (ref "U1") (pin "71") (pinfunction "14.4_71") (pintype "passive+no_connect"))
    )
    (net (code "104") (name "unconnected-(U1-14.5-Pad72)") (class "Default")
      (node (ref "U1") (pin "72") (pinfunction "14.5_72") (pintype "passive+no_connect"))
    )
    (net (code "105") (name "unconnected-(U1-14.6-Pad73)") (class "Default")
      (node (ref "U1") (pin "73") (pinfunction "14.6_73") (pintype "passive+no_connect"))
    )
    (net (code "106") (name "unconnected-(U1-15.6-Pad64)") (class "Default")
      (node (ref "U1") (pin "64") (pinfunction "15.6_64") (pintype "passive"))
    )
    (net (code "107") (name "unconnected-(U1-15.7-Pad65)") (class "Default")
      (node (ref "U1") (pin "65") (pinfunction "15.7_65") (pintype "passive"))
    )
    (net (code "108") (name "unconnected-(U1-15.8-Pad66)") (class "Default")
      (node (ref "U1") (pin "66") (pinfunction "15.8_66") (pintype "passive"))
    )
    (net (code "109") (name "unconnected-(U1-20.2-Pad45)") (class "Default")
      (node (ref "U1") (pin "45") (pinfunction "20.2_45") (pintype "passive+no_connect"))
    )
    (net (code "110") (name "unconnected-(U1-20.3-Pad46)") (class "Default")
      (node (ref "U1") (pin "46") (pinfunction "20.3_46") (pintype "passive"))
    )
    (net (code "111") (name "unconnected-(U1-20.6-Pad49)") (class "Default")
      (node (ref "U1") (pin "49") (pinfunction "20.6_49") (pintype "passive"))
    )
    (net (code "112") (name "unconnected-(U1-20.7-Pad50)") (class "Default")
      (node (ref "U1") (pin "50") (pinfunction "20.7_50") (pintype "passive"))
    )
    (net (code "113") (name "unconnected-(U1-20.8-Pad51)") (class "Default")
      (node (ref "U1") (pin "51") (pinfunction "20.8_51") (pintype "passive+no_connect"))
    )
    (net (code "114") (name "unconnected-(U1-20.9-Pad52)") (class "Default")
      (node (ref "U1") (pin "52") (pinfunction "20.9_52") (pintype "passive+no_connect"))
    )
    (net (code "115") (name "unconnected-(U1-20.10-Pad53)") (class "Default")
      (node (ref "U1") (pin "53") (pinfunction "20.10_53") (pintype "passive"))
    )
    (net (code "116") (name "unconnected-(U1-21.2-Pad38)") (class "Default")
      (node (ref "U1") (pin "38") (pinfunction "21.2_38") (pintype "passive"))
    )
    (net (code "117") (name "unconnected-(U1-21.3-Pad39)") (class "Default")
      (node (ref "U1") (pin "39") (pinfunction "21.3_39") (pintype "passive"))
    )
    (net (code "118") (name "unconnected-(U1-21.4-Pad40)") (class "Default")
      (node (ref "U1") (pin "40") (pinfunction "21.4_40") (pintype "passive"))
    )
    (net (code "119") (name "unconnected-(U1-21.5-Pad41)") (class "Default")
      (node (ref "U1") (pin "41") (pinfunction "21.5_41") (pintype "passive"))
    )
    (net (code "120") (name "unconnected-(U1-21.7-Pad43)") (class "Default")
      (node (ref "U1") (pin "43") (pinfunction "21.7_43") (pintype "passive"))
    )
    (net (code "121") (name "unconnected-(U1-22.1-Pad35)") (class "Default")
      (node (ref "U1") (pin "35") (pinfunction "22.1_35") (pintype "passive"))
    )
    (net (code "122") (name "unconnected-(U1-22.3-Pad37)") (class "Default")
      (node (ref "U1") (pin "37") (pinfunction "22.3_37") (pintype "passive"))
    )
    (net (code "123") (name "unconnected-(U1-33.4-Pad22)") (class "Default")
      (node (ref "U1") (pin "22") (pinfunction "33.4_22") (pintype "passive"))
    )
    (net (code "124") (name "unconnected-(U1-A2-Pad19)") (class "Default")
      (node (ref "U1") (pin "19") (pinfunction "A2_19") (pintype "passive"))
    )
    (net (code "125") (name "unconnected-(U1-A3-Pad18)") (class "Default")
      (node (ref "U1") (pin "18") (pinfunction "A3_18") (pintype "passive"))
    )
    (net (code "126") (name "unconnected-(U1-A4-Pad17)") (class "Default")
      (node (ref "U1") (pin "17") (pinfunction "A4_17") (pintype "passive"))
    )
    (net (code "127") (name "unconnected-(U1-A5-Pad16)") (class "Default")
      (node (ref "U1") (pin "16") (pinfunction "A5_16") (pintype "passive"))
    )
    (net (code "128") (name "unconnected-(U1-A6-Pad15)") (class "Default")
      (node (ref "U1") (pin "15") (pinfunction "A6_15") (pintype "passive"))
    )
    (net (code "129") (name "unconnected-(U1-A7-Pad14)") (class "Default")
      (node (ref "U1") (pin "14") (pinfunction "A7_14") (pintype "passive"))
    )
    (net (code "130") (name "unconnected-(U1-A8-Pad13)") (class "Default")
      (node (ref "U1") (pin "13") (pinfunction "A8_13") (pintype "passive"))
    )
    (net (code "131") (name "unconnected-(U1-A10-Pad12)") (class "Default")
      (node (ref "U1") (pin "12") (pinfunction "A10_12") (pintype "passive"))
    )
    (net (code "132") (name "unconnected-(U1-A11-Pad11)") (class "Default")
      (node (ref "U1") (pin "11") (pinfunction "A11_11") (pintype "passive"))
    )
    (net (code "133") (name "unconnected-(U1-A12-Pad10)") (class "Default")
      (node (ref "U1") (pin "10") (pinfunction "A12_10") (pintype "passive"))
    )
    (net (code "134") (name "unconnected-(U1-A13-Pad9)") (class "Default")
      (node (ref "U1") (pin "9") (pinfunction "A13_9") (pintype "passive"))
    )
    (net (code "135") (name "unconnected-(U1-A16-Pad8)") (class "Default")
      (node (ref "U1") (pin "8") (pinfunction "A16_8") (pintype "passive"))
    )
    (net (code "136") (name "unconnected-(U1-A17-Pad7)") (class "Default")
      (node (ref "U1") (pin "7") (pinfunction "A17_7") (pintype "passive"))
    )
    (net (code "137") (name "unconnected-(U1-A20-Pad6)") (class "Default")
      (node (ref "U1") (pin "6") (pinfunction "A20_6") (pintype "passive"))
    )
    (net (code "138") (name "unconnected-(U1-A21-Pad5)") (class "Default")
      (node (ref "U1") (pin "5") (pinfunction "A21_5") (pintype "passive"))
    )
    (net (code "139") (name "unconnected-(U1-A24-Pad122)") (class "Default")
      (node (ref "U1") (pin "122") (pinfunction "A24_122") (pintype "passive"))
    )
    (net (code "140") (name "unconnected-(U1-A25-Pad121)") (class "Default")
      (node (ref "U1") (pin "121") (pinfunction "A25_121") (pintype "passive"))
    )
    (net (code "141") (name "unconnected-(U1-A35-Pad120)") (class "Default")
      (node (ref "U1") (pin "120") (pinfunction "A35_120") (pintype "passive"))
    )
    (net (code "142") (name "unconnected-(U1-A36-Pad119)") (class "Default")
      (node (ref "U1") (pin "119") (pinfunction "A36_119") (pintype "passive"))
    )
    (net (code "143") (name "unconnected-(U1-A37-Pad118)") (class "Default")
      (node (ref "U1") (pin "118") (pinfunction "A37_118") (pintype "passive"))
    )
    (net (code "144") (name "unconnected-(U1-A38-Pad117)") (class "Default")
      (node (ref "U1") (pin "117") (pinfunction "A38_117") (pintype "passive"))
    )
    (net (code "145") (name "unconnected-(U1-A39-Pad116)") (class "Default")
      (node (ref "U1") (pin "116") (pinfunction "A39_116") (pintype "passive"))
    )
    (net (code "146") (name "unconnected-(U1-A42-Pad115)") (class "Default")
      (node (ref "U1") (pin "115") (pinfunction "A42_115") (pintype "passive"))
    )
    (net (code "147") (name "unconnected-(U1-A43-Pad114)") (class "Default")
      (node (ref "U1") (pin "114") (pinfunction "A43_114") (pintype "passive"))
    )
    (net (code "148") (name "unconnected-(U1-A44-Pad113)") (class "Default")
      (node (ref "U1") (pin "113") (pinfunction "A44_113") (pintype "passive"))
    )
    (net (code "149") (name "unconnected-(U1-A45-Pad112)") (class "Default")
      (node (ref "U1") (pin "112") (pinfunction "A45_112") (pintype "passive"))
    )
    (net (code "150") (name "unconnected-(U1-A46-Pad111)") (class "Default")
      (node (ref "U1") (pin "111") (pinfunction "A46_111") (pintype "passive"))
    )
    (net (code "151") (name "unconnected-(U1-A47-Pad110)") (class "Default")
      (node (ref "U1") (pin "110") (pinfunction "A47_110") (pintype "passive"))
    )
    (net (code "152") (name "unconnected-(U1-ESR0-Pad48)") (class "Default")
      (node (ref "U1") (pin "48") (pinfunction "ESR0_48") (pintype "passive"))
    )
    (net (code "153") (name "unconnected-(U1-ESR1-Pad47)") (class "Default")
      (node (ref "U1") (pin "47") (pinfunction "ESR1_47") (pintype "passive"))
    )
    (net (code "154") (name "unconnected-(U3-NC-Pad4)") (class "Default")
      (node (ref "U3") (pin "4") (pinfunction "NC_4") (pintype "passive+no_connect"))
    )
    (net (code "155") (name "unconnected-(U4-NC-Pad4)") (class "Default")
      (node (ref "U4") (pin "4") (pinfunction "NC_4") (pintype "passive+no_connect"))
    )
    (net (code "156") (name "unconnected-(Wireless1-CMD-Pad8)") (class "Default")
      (node (ref "Wireless1") (pin "8") (pinfunction "CMD_8") (pintype "passive+no_connect"))
    )
    (net (code "157") (name "unconnected-(Wireless1-NC-Pad2)") (class "Default")
      (node (ref "Wireless1") (pin "2") (pinfunction "NC_2") (pintype "passive+no_connect"))
    )
  )
)
